# Sheet1.net
KiCad netlist of a schematic drawn in Altium Designer
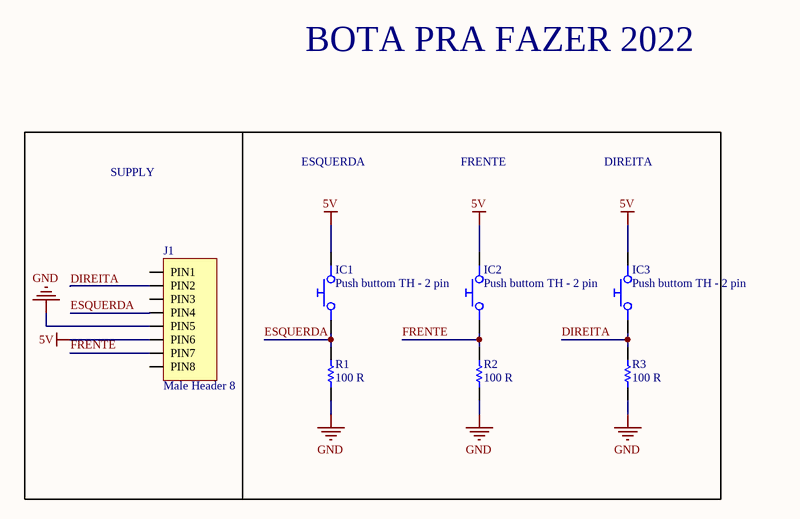
[diagram p0: Sheet1.SchDoc]

(export (version "E")
  (design (tool "Eeschema 10.0.6"))
  (components
    (comp (ref "IC1")
      (value "Push buttom TH - 2 pin")
      (footprint "BUTTON - TH - 2PIN")
      (description "Push buttom true hole with 2 pin")
      (fields (field (name "MANUFACTURER_PART_NUMBER") "TS02-66-90-BK-100-SCR-D"))
      (libsource (lib "Uai!Tecas") (part "Push buttom TH - 2 pin"))
    )
    (comp (ref "IC2")
      (value "Push buttom TH - 2 pin")
      (footprint "BUTTON - TH - 2PIN")
      (description "Push buttom true hole with 2 pin")
      (fields (field (name "MANUFACTURER_PART_NUMBER") "TS02-66-90-BK-100-SCR-D"))
      (libsource (lib "Uai!Tecas") (part "Push buttom TH - 2 pin"))
    )
    (comp (ref "IC3")
      (value "Push buttom TH - 2 pin")
      (footprint "BUTTON - TH - 2PIN")
      (description "Push buttom true hole with 2 pin")
      (fields (field (name "MANUFACTURER_PART_NUMBER") "TS02-66-90-BK-100-SCR-D"))
      (libsource (lib "Uai!Tecas") (part "Push buttom TH - 2 pin"))
    )
    (comp (ref "J1")
      (value "Male Header 8")
      (footprint "MALE HEADER 8")
      (fields
        (field (name "LIBRARY CONTROL - PERSON THAT DID THE LAST UPDATE SCHEMATIC") "Marcos")
        (field (name "LIBRARY CONTROL - PERSONT THAT DID THE LAST UPDATE FOOTPRINT") "Marcos")
      )
      (libsource (lib "Uai!Tecas") (part "Male Header 8"))
    )
    (comp (ref "R1")
      (value "100 R")
      (footprint "RESISTOR_THROUGH_HOLE")
      (description "RES PTH 100 OHM 5% 3W")
      (fields
        (field (name "MANUFACTURER") "Vishay / BC Components")
        (field (name "PART NUMBER") "PR03000201000JAC00")
        (field (name "LIBRARY CONTROL - PERSON THAT CHECKED FOOTPRINT") "Nikaum")
        (field (name "LIBRARY CONTROL - PERSON THAT CHECKED SCHEMATIC") "Nikaum")
        (field (name "LIBRARY CONTROL - PERSON THAT DID THE LAST UPDATE FOOTPRINT") "Nikaum")
        (field (name "LIBRARY CONTROL - PERSON THAT DID THE LAST UPDATE SCHEMATIC") "Nikaum")
      )
      (libsource (lib "Uai!Tecas") (part "PR03000201000JAC00"))
    )
    (comp (ref "R2")
      (value "100 R")
      (footprint "RESISTOR_THROUGH_HOLE")
      (description "RES PTH 100 OHM 5% 3W")
      (fields
        (field (name "MANUFACTURER") "Vishay / BC Components")
        (field (name "PART NUMBER") "PR03000201000JAC00")
        (field (name "LIBRARY CONTROL - PERSON THAT CHECKED FOOTPRINT") "Nikaum")
        (field (name "LIBRARY CONTROL - PERSON THAT CHECKED SCHEMATIC") "Nikaum")
        (field (name "LIBRARY CONTROL - PERSON THAT DID THE LAST UPDATE FOOTPRINT") "Nikaum")
        (field (name "LIBRARY CONTROL - PERSON THAT DID THE LAST UPDATE SCHEMATIC") "Nikaum")
      )
      (libsource (lib "Uai!Tecas") (part "PR03000201000JAC00"))
    )
    (comp (ref "R3")
      (value "100 R")
      (footprint "RESISTOR_THROUGH_HOLE")
      (description "RES PTH 100 OHM 5% 3W")
      (fields
        (field (name "MANUFACTURER") "Vishay / BC Components")
        (field (name "PART NUMBER") "PR03000201000JAC00")
        (field (name "LIBRARY CONTROL - PERSON THAT CHECKED FOOTPRINT") "Nikaum")
        (field (name "LIBRARY CONTROL - PERSON THAT CHECKED SCHEMATIC") "Nikaum")
        (field (name "LIBRARY CONTROL - PERSON THAT DID THE LAST UPDATE FOOTPRINT") "Nikaum")
        (field (name "LIBRARY CONTROL - PERSON THAT DID THE LAST UPDATE SCHEMATIC") "Nikaum")
      )
      (libsource (lib "Uai!Tecas") (part "PR03000201000JAC00"))
    )
  )
  (nets
    (net (code "1") (name "/DIREITA") (class "Default")
      (node (ref "IC3") (pin "1") (pinfunction "1_1") (pintype "passive"))
      (node (ref "J1") (pin "PIN2") (pinfunction "PIN2_PIN2") (pintype "passive"))
      (node (ref "R3") (pin "2") (pinfunction "2_2") (pintype "passive"))
    )
    (net (code "2") (name "/ESQUERDA") (class "Default")
      (node (ref "IC1") (pin "1") (pinfunction "1_1") (pintype "passive"))
      (node (ref "J1") (pin "PIN4") (pinfunction "PIN4_PIN4") (pintype "passive"))
      (node (ref "R1") (pin "2") (pinfunction "2_2") (pintype "passive"))
    )
    (net (code "3") (name "/FRENTE") (class "Default")
      (node (ref "IC2") (pin "1") (pinfunction "1_1") (pintype "passive"))
      (node (ref "J1") (pin "PIN7") (pinfunction "PIN7_PIN7") (pintype "passive"))
      (node (ref "R2") (pin "2") (pinfunction "2_2") (pintype "passive"))
    )
    (net (code "4") (name "5V") (class "Default")
      (node (ref "IC1") (pin "2") (pinfunction "2_2") (pintype "passive"))
      (node (ref "IC2") (pin "2") (pinfunction "2_2") (pintype "passive"))
      (node (ref "IC3") (pin "2") (pinfunction "2_2") (pintype "passive"))
      (node (ref "J1") (pin "PIN6") (pinfunction "PIN6_PIN6") (pintype "passive"))
    )
    (net (code "5") (name "GND") (class "Default")
      (node (ref "J1") (pin "PIN5") (pinfunction "PIN5_PIN5") (pintype "passive"))
      (node (ref "R1") (pin "1") (pinfunction "1_1") (pintype "passive"))
      (node (ref "R2") (pin "1") (pinfunction "1_1") (pintype "passive"))
      (node (ref "R3") (pin "1") (pinfunction "1_1") (pintype "passive"))
    )
    (net (code "6") (name "unconnected-(J1-PadPIN1)") (class "Default")
      (node (ref "J1") (pin "PIN1") (pinfunction "PIN1_PIN1") (pintype "passive"))
    )
    (net (code "7") (name "unconnected-(J1-PadPIN3)") (class "Default")
      (node (ref "J1") (pin "PIN3") (pinfunction "PIN3_PIN3") (pintype "passive"))
    )
    (net (code "8") (name "unconnected-(J1-PadPIN8)") (class "Default")
      (node (ref "J1") (pin "PIN8") (pinfunction "PIN8_PIN8") (pintype "passive"))
    )
  )
)
